# extensionBoard.net
KiCad netlist of a schematic drawn in Altium Designer
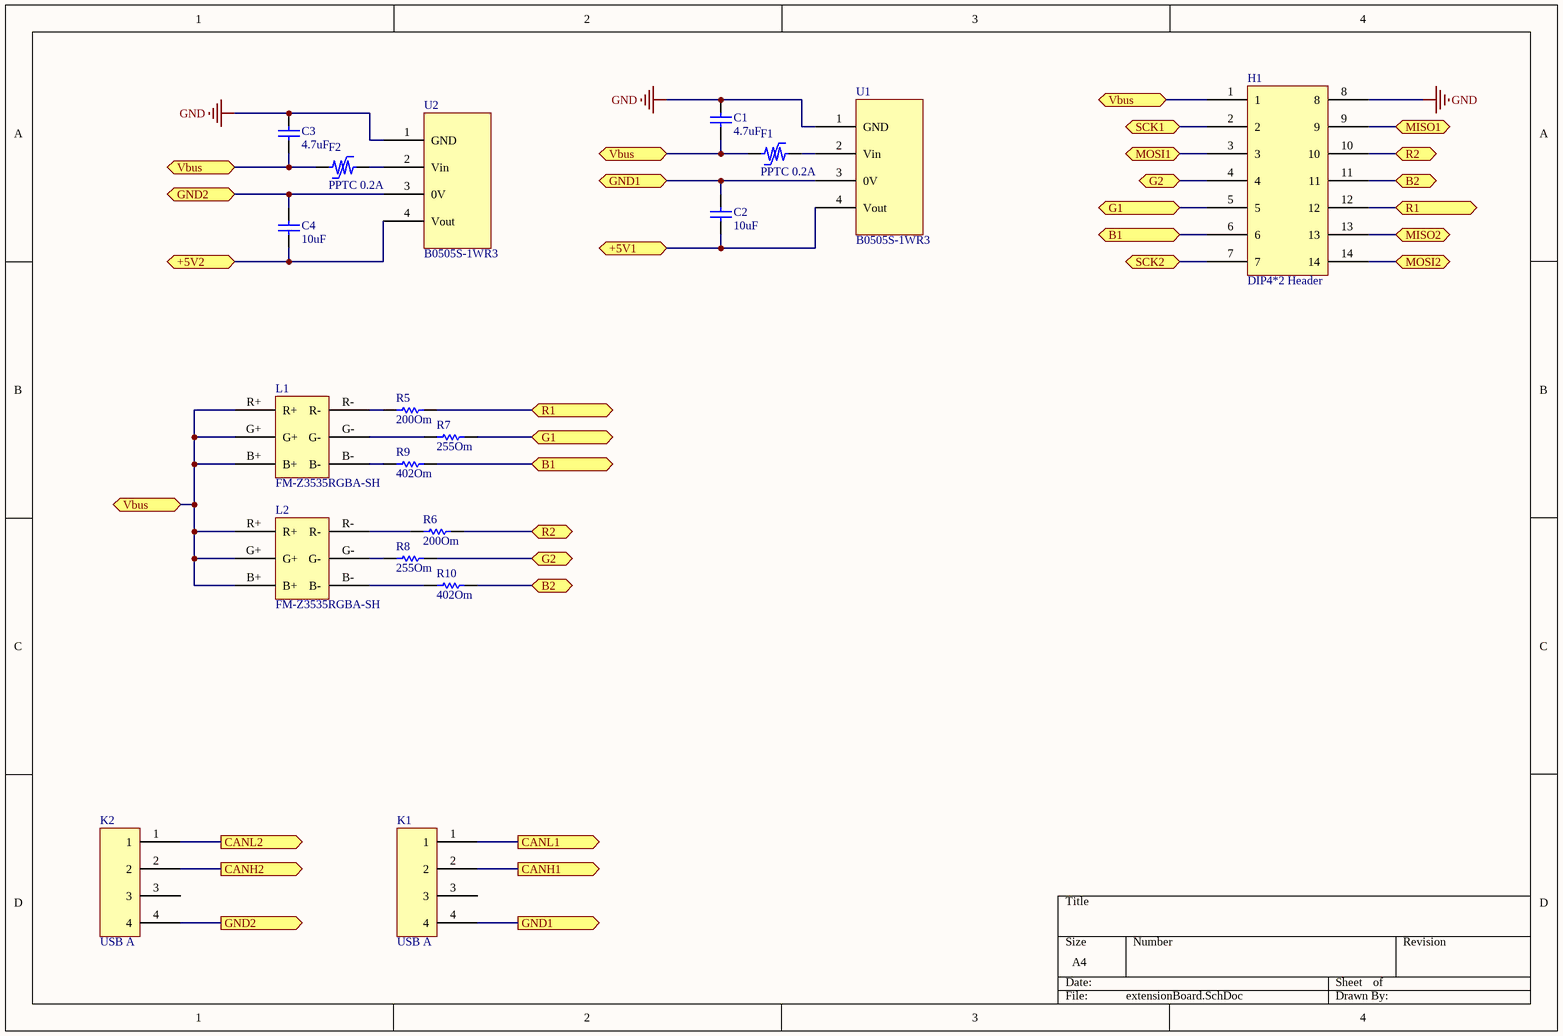
[diagram p0: extensionBoard.SchDoc]

(export (version "E")
  (design (tool "Eeschema 10.0.6"))
  (components
    (comp (ref "C1")
      (value "4.7uF")
      (footprint "CAPC1608X90X35ML10T15")
      (fields (field (name "MANUFACTURER") "Murata") (field (name "PART NUMBER") "GCM1885C2A101JA16D"))
      (libsource (lib "Altium Content Vault") (part "CAP"))
    )
    (comp (ref "C2")
      (value "10uF")
      (footprint "CAPC1608X90X35ML10T15")
      (fields (field (name "MANUFACTURER") "Murata") (field (name "PART NUMBER") "GCM1885C2A101JA16D"))
      (libsource (lib "Altium Content Vault") (part "CAP"))
    )
    (comp (ref "C3")
      (value "4.7uF")
      (footprint "CAPC1608X90X35ML10T15")
      (fields (field (name "MANUFACTURER") "Murata") (field (name "PART NUMBER") "GCM1885C2A101JA16D"))
      (libsource (lib "Altium Content Vault") (part "CAP"))
    )
    (comp (ref "C4")
      (value "10uF")
      (footprint "CAPC1608X90X35ML10T15")
      (fields (field (name "MANUFACTURER") "Murata") (field (name "PART NUMBER") "GCM1885C2A101JA16D"))
      (libsource (lib "Altium Content Vault") (part "CAP"))
    )
    (comp (ref "F1")
      (value "PPTC 0.2A")
      (footprint "PTC 0603")
      (libsource (lib "lib") (part "PTC Resettable Fuse"))
    )
    (comp (ref "F2")
      (value "PPTC 0.2A")
      (footprint "PTC 0603")
      (libsource (lib "lib") (part "PTC Resettable Fuse"))
    )
    (comp (ref "H1")
      (value "DIP4*2 Header")
      (footprint "DIP7*2")
      (libsource (lib "lib") (part "DIP4*2 Header"))
    )
    (comp (ref "K1") (value "USB A") (footprint "USB A") (libsource (lib "lib") (part "USB A")))
    (comp (ref "K2") (value "USB A") (footprint "USB A") (libsource (lib "lib") (part "USB A")))
    (comp (ref "L1")
      (value "FM-Z3535RGBA-SH")
      (footprint "Z3535RGBA")
      (libsource (lib "lib") (part "FM-Z3535RGBA-SH"))
    )
    (comp (ref "L2")
      (value "FM-Z3535RGBA-SH")
      (footprint "Z3535RGBA")
      (libsource (lib "lib") (part "FM-Z3535RGBA-SH"))
    )
    (comp (ref "R5")
      (value "200Om")
      (footprint "RESC1608X55X30ML20T10")
      (fields (field (name "PART NUMBER") "RK73H1JTTD5101F") (field (name "MANUFACTURER") "KOA Speer"))
      (libsource (lib "Altium Content Vault") (part "RES"))
    )
    (comp (ref "R6")
      (value "200Om")
      (footprint "RESC1608X55X30ML20T10")
      (fields (field (name "PART NUMBER") "RK73H1JTTD5101F") (field (name "MANUFACTURER") "KOA Speer"))
      (libsource (lib "Altium Content Vault") (part "RES"))
    )
    (comp (ref "R7")
      (value "255Om")
      (footprint "RESC1608X55X30ML20T10")
      (fields (field (name "PART NUMBER") "RK73H1JTTD5101F") (field (name "MANUFACTURER") "KOA Speer"))
      (libsource (lib "Altium Content Vault") (part "RES"))
    )
    (comp (ref "R8")
      (value "255Om")
      (footprint "RESC1608X55X30ML20T10")
      (fields (field (name "PART NUMBER") "RK73H1JTTD5101F") (field (name "MANUFACTURER") "KOA Speer"))
      (libsource (lib "Altium Content Vault") (part "RES"))
    )
    (comp (ref "R9")
      (value "402Om")
      (footprint "RESC1608X55X30ML20T10")
      (fields (field (name "PART NUMBER") "RK73H1JTTD5101F") (field (name "MANUFACTURER") "KOA Speer"))
      (libsource (lib "Altium Content Vault") (part "RES"))
    )
    (comp (ref "R10")
      (value "402Om")
      (footprint "RESC1608X55X30ML20T10")
      (fields (field (name "PART NUMBER") "RK73H1JTTD5101F") (field (name "MANUFACTURER") "KOA Speer"))
      (libsource (lib "Altium Content Vault") (part "RES"))
    )
    (comp (ref "U1")
      (value "B0505S-1WR3")
      (footprint "Dip4 package")
      (libsource (lib "lib") (part "B0505S-1WR3"))
    )
    (comp (ref "U2")
      (value "B0505S-1WR3")
      (footprint "Dip4 package")
      (libsource (lib "lib") (part "B0505S-1WR3"))
    )
  )
  (nets
    (net (code "1") (name "/+5V1") (class "Default")
      (node (ref "C2") (pin "1") (pinfunction "1_1") (pintype "passive"))
      (node (ref "U1") (pin "4") (pinfunction "Vout_4") (pintype "passive"))
    )
    (net (code "2") (name "/+5V2") (class "Default")
      (node (ref "C4") (pin "1") (pinfunction "1_1") (pintype "passive"))
      (node (ref "U2") (pin "4") (pinfunction "Vout_4") (pintype "passive"))
    )
    (net (code "3") (name "/B1") (class "Default")
      (node (ref "H1") (pin "6") (pinfunction "6_6") (pintype "passive"))
      (node (ref "R9") (pin "2") (pinfunction "2_2") (pintype "passive"))
    )
    (net (code "4") (name "/B2") (class "Default")
      (node (ref "H1") (pin "11") (pinfunction "11_11") (pintype "passive"))
      (node (ref "R10") (pin "2") (pinfunction "2_2") (pintype "passive"))
    )
    (net (code "5") (name "/CANH1") (class "Default")
      (node (ref "K1") (pin "2") (pinfunction "2_2") (pintype "passive"))
    )
    (net (code "6") (name "/CANH2") (class "Default")
      (node (ref "K2") (pin "2") (pinfunction "2_2") (pintype "passive"))
    )
    (net (code "7") (name "/CANL1") (class "Default")
      (node (ref "K1") (pin "1") (pinfunction "1_1") (pintype "passive"))
    )
    (net (code "8") (name "/CANL2") (class "Default")
      (node (ref "K2") (pin "1") (pinfunction "1_1") (pintype "passive"))
    )
    (net (code "9") (name "/G1") (class "Default")
      (node (ref "H1") (pin "5") (pinfunction "5_5") (pintype "passive"))
      (node (ref "R7") (pin "2") (pinfunction "2_2") (pintype "passive"))
    )
    (net (code "10") (name "/G2") (class "Default")
      (node (ref "H1") (pin "4") (pinfunction "4_4") (pintype "passive"))
      (node (ref "R8") (pin "2") (pinfunction "2_2") (pintype "passive"))
    )
    (net (code "11") (name "/GND1") (class "Default")
      (node (ref "C2") (pin "2") (pinfunction "2_2") (pintype "passive"))
      (node (ref "K1") (pin "4") (pinfunction "4_4") (pintype "passive"))
      (node (ref "U1") (pin "3") (pinfunction "0V_3") (pintype "passive"))
    )
    (net (code "12") (name "/GND2") (class "Default")
      (node (ref "C4") (pin "2") (pinfunction "2_2") (pintype "passive"))
      (node (ref "K2") (pin "4") (pinfunction "4_4") (pintype "passive"))
      (node (ref "U2") (pin "3") (pinfunction "0V_3") (pintype "passive"))
    )
    (net (code "13") (name "/MISO1") (class "Default")
      (node (ref "H1") (pin "9") (pinfunction "9_9") (pintype "passive"))
    )
    (net (code "14") (name "/MISO2") (class "Default")
      (node (ref "H1") (pin "13") (pinfunction "13_13") (pintype "passive"))
    )
    (net (code "15") (name "/MOSI1") (class "Default")
      (node (ref "H1") (pin "3") (pinfunction "3_3") (pintype "passive"))
    )
    (net (code "16") (name "/MOSI2") (class "Default")
      (node (ref "H1") (pin "14") (pinfunction "14_14") (pintype "passive"))
    )
    (net (code "17") (name "/R1") (class "Default")
      (node (ref "H1") (pin "12") (pinfunction "12_12") (pintype "passive"))
      (node (ref "R5") (pin "2") (pinfunction "2_2") (pintype "passive"))
    )
    (net (code "18") (name "/R2") (class "Default")
      (node (ref "H1") (pin "10") (pinfunction "10_10") (pintype "passive"))
      (node (ref "R6") (pin "2") (pinfunction "2_2") (pintype "passive"))
    )
    (net (code "19") (name "/SCK1") (class "Default")
      (node (ref "H1") (pin "2") (pinfunction "2_2") (pintype "passive"))
    )
    (net (code "20") (name "/SCK2") (class "Default")
      (node (ref "H1") (pin "7") (pinfunction "7_7") (pintype "passive"))
    )
    (net (code "21") (name "/Vbus") (class "Default")
      (node (ref "C1") (pin "1") (pinfunction "1_1") (pintype "passive"))
      (node (ref "C3") (pin "1") (pinfunction "1_1") (pintype "passive"))
      (node (ref "F1") (pin "1") (pinfunction "1_1") (pintype "passive"))
      (node (ref "F2") (pin "1") (pinfunction "1_1") (pintype "passive"))
      (node (ref "H1") (pin "1") (pinfunction "1_1") (pintype "passive"))
      (node (ref "L1") (pin "B+") (pinfunction "B+_B+") (pintype "passive"))
      (node (ref "L1") (pin "G+") (pinfunction "G+_G+") (pintype "passive"))
      (node (ref "L1") (pin "R+") (pinfunction "R+_R+") (pintype "passive"))
      (node (ref "L2") (pin "B+") (pinfunction "B+_B+") (pintype "passive"))
      (node (ref "L2") (pin "G+") (pinfunction "G+_G+") (pintype "passive"))
      (node (ref "L2") (pin "R+") (pinfunction "R+_R+") (pintype "passive"))
    )
    (net (code "22") (name "GND") (class "Default")
      (node (ref "C1") (pin "2") (pinfunction "2_2") (pintype "passive"))
      (node (ref "C3") (pin "2") (pinfunction "2_2") (pintype "passive"))
      (node (ref "H1") (pin "8") (pinfunction "8_8") (pintype "passive"))
      (node (ref "U1") (pin "1") (pinfunction "GND_1") (pintype "passive"))
      (node (ref "U2") (pin "1") (pinfunction "GND_1") (pintype "passive"))
    )
    (net (code "23") (name "Net-(L1-PadB-)") (class "Default")
      (node (ref "L1") (pin "B-") (pinfunction "B-_B-") (pintype "passive"))
      (node (ref "R9") (pin "1") (pinfunction "1_1") (pintype "passive"))
    )
    (net (code "24") (name "Net-(L1-PadG-)") (class "Default")
      (node (ref "L1") (pin "G-") (pinfunction "G-_G-") (pintype "passive"))
      (node (ref "R7") (pin "1") (pinfunction "1_1") (pintype "passive"))
    )
    (net (code "25") (name "Net-(L1-PadR-)") (class "Default")
      (node (ref "L1") (pin "R-") (pinfunction "R-_R-") (pintype "passive"))
      (node (ref "R5") (pin "1") (pinfunction "1_1") (pintype "passive"))
    )
    (net (code "26") (name "Net-(L2-PadB-)") (class "Default")
      (node (ref "L2") (pin "B-") (pinfunction "B-_B-") (pintype "passive"))
      (node (ref "R10") (pin "1") (pinfunction "1_1") (pintype "passive"))
    )
    (net (code "27") (name "Net-(L2-PadG-)") (class "Default")
      (node (ref "L2") (pin "G-") (pinfunction "G-_G-") (pintype "passive"))
      (node (ref "R8") (pin "1") (pinfunction "1_1") (pintype "passive"))
    )
    (net (code "28") (name "Net-(L2-PadR-)") (class "Default")
      (node (ref "L2") (pin "R-") (pinfunction "R-_R-") (pintype "passive"))
      (node (ref "R6") (pin "1") (pinfunction "1_1") (pintype "passive"))
    )
    (net (code "29") (name "Net-(U1-Vin)") (class "Default")
      (node (ref "F1") (pin "2") (pinfunction "2_2") (pintype "passive"))
      (node (ref "U1") (pin "2") (pinfunction "Vin_2") (pintype "passive"))
    )
    (net (code "30") (name "Net-(U2-Vin)") (class "Default")
      (node (ref "F2") (pin "2") (pinfunction "2_2") (pintype "passive"))
      (node (ref "U2") (pin "2") (pinfunction "Vin_2") (pintype "passive"))
    )
    (net (code "31") (name "unconnected-(K1-Pad3)") (class "Default")
      (node (ref "K1") (pin "3") (pinfunction "3_3") (pintype "passive"))
    )
    (net (code "32") (name "unconnected-(K2-Pad3)") (class "Default")
      (node (ref "K2") (pin "3") (pinfunction "3_3") (pintype "passive"))
    )
  )
)
